# sousvide.net
KiCad netlist of a schematic drawn in EAGLE
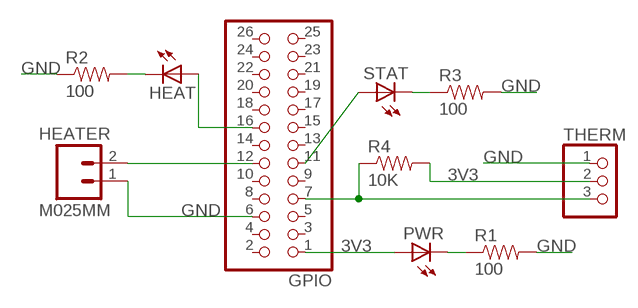
[diagram p0: schematic, sheet 1]

(export (version "E")
  (design (tool "Eeschema 10.0.6"))
  (components
    (comp (ref "GPIO")
      (value "PINHD-2X13")
      (footprint "eagle-import:2X13")
      (libsource (lib "eagle-import") (part "PINHD-2X13"))
    )
    (comp (ref "HEAT")
      (value "LED1206")
      (footprint "eagle-import:LED-1206")
      (libsource (lib "eagle-import") (part "LED1206"))
    )
    (comp (ref "HEATER")
      (value "M025MM")
      (footprint "eagle-import:SCREWTERMINAL-5MM-2")
      (libsource (lib "eagle-import") (part "M025MM"))
    )
    (comp (ref "PWR")
      (value "LED1206")
      (footprint "eagle-import:LED-1206")
      (libsource (lib "eagle-import") (part "LED1206"))
    )
    (comp (ref "R1")
      (value "100")
      (footprint "eagle-import:1206")
      (libsource (lib "eagle-import") (part "RESISTOR1206"))
    )
    (comp (ref "R2")
      (value "100")
      (footprint "eagle-import:1206")
      (libsource (lib "eagle-import") (part "SparkFun-Resistors_RESISTOR1206"))
    )
    (comp (ref "R3")
      (value "100")
      (footprint "eagle-import:1206")
      (libsource (lib "eagle-import") (part "RESISTOR1206"))
    )
    (comp (ref "R4")
      (value "10K")
      (footprint "eagle-import:1206")
      (libsource (lib "eagle-import") (part "RESISTOR1206"))
    )
    (comp (ref "STAT")
      (value "LED1206")
      (footprint "eagle-import:LED-1206")
      (libsource (lib "eagle-import") (part "LED1206"))
    )
    (comp (ref "THERM")
      (value "PINHD-1X3")
      (footprint "eagle-import:1X03")
      (libsource (lib "eagle-import") (part "PINHD-1X3"))
    )
  )
  (nets
    (net (code "1") (name "/3V3") (class "Default")
      (node (ref "GPIO") (pin "1") (pinfunction "1_1") (pintype "passive"))
      (node (ref "PWR") (pin "A") (pinfunction "A_A") (pintype "passive"))
      (node (ref "R4") (pin "2") (pinfunction "2_2") (pintype "passive"))
      (node (ref "THERM") (pin "2") (pinfunction "2_2") (pintype "passive"))
    )
    (net (code "2") (name "/GND") (class "Default")
      (node (ref "GPIO") (pin "6") (pinfunction "6_6") (pintype "passive"))
      (node (ref "HEATER") (pin "1") (pinfunction "1_1") (pintype "passive"))
      (node (ref "R1") (pin "2") (pinfunction "2_2") (pintype "passive"))
      (node (ref "R2") (pin "1") (pinfunction "1_1") (pintype "passive"))
      (node (ref "R3") (pin "2") (pinfunction "2_2") (pintype "passive"))
      (node (ref "THERM") (pin "1") (pinfunction "1_1") (pintype "passive"))
    )
    (net (code "3") (name "Net-(GPIO-Pad7)") (class "Default")
      (node (ref "GPIO") (pin "7") (pinfunction "7_7") (pintype "passive"))
      (node (ref "R4") (pin "1") (pinfunction "1_1") (pintype "passive"))
      (node (ref "THERM") (pin "3") (pinfunction "3_3") (pintype "passive"))
    )
    (net (code "4") (name "Net-(GPIO-Pad11)") (class "Default")
      (node (ref "GPIO") (pin "11") (pinfunction "11_11") (pintype "passive"))
      (node (ref "STAT") (pin "A") (pinfunction "A_A") (pintype "passive"))
    )
    (net (code "5") (name "Net-(GPIO-Pad12)") (class "Default")
      (node (ref "GPIO") (pin "12") (pinfunction "12_12") (pintype "passive"))
      (node (ref "HEATER") (pin "2") (pinfunction "2_2") (pintype "passive"))
    )
    (net (code "6") (name "Net-(GPIO-Pad16)") (class "Default")
      (node (ref "GPIO") (pin "16") (pinfunction "16_16") (pintype "passive"))
      (node (ref "HEAT") (pin "A") (pinfunction "A_A") (pintype "passive"))
    )
    (net (code "7") (name "Net-(HEAT-PadC)") (class "Default")
      (node (ref "HEAT") (pin "C") (pinfunction "C_C") (pintype "passive"))
      (node (ref "R2") (pin "2") (pinfunction "2_2") (pintype "passive"))
    )
    (net (code "8") (name "Net-(PWR-PadC)") (class "Default")
      (node (ref "PWR") (pin "C") (pinfunction "C_C") (pintype "passive"))
      (node (ref "R1") (pin "1") (pinfunction "1_1") (pintype "passive"))
    )
    (net (code "9") (name "Net-(R3-Pad1)") (class "Default")
      (node (ref "R3") (pin "1") (pinfunction "1_1") (pintype "passive"))
      (node (ref "STAT") (pin "C") (pinfunction "C_C") (pintype "passive"))
    )
    (net (code "10") (name "unconnected-(GPIO-Pad2)") (class "Default")
      (node (ref "GPIO") (pin "2") (pinfunction "2_2") (pintype "passive"))
    )
    (net (code "11") (name "unconnected-(GPIO-Pad3)") (class "Default")
      (node (ref "GPIO") (pin "3") (pinfunction "3_3") (pintype "passive"))
    )
    (net (code "12") (name "unconnected-(GPIO-Pad4)") (class "Default")
      (node (ref "GPIO") (pin "4") (pinfunction "4_4") (pintype "passive"))
    )
    (net (code "13") (name "unconnected-(GPIO-Pad5)") (class "Default")
      (node (ref "GPIO") (pin "5") (pinfunction "5_5") (pintype "passive"))
    )
    (net (code "14") (name "unconnected-(GPIO-Pad8)") (class "Default")
      (node (ref "GPIO") (pin "8") (pinfunction "8_8") (pintype "passive"))
    )
    (net (code "15") (name "unconnected-(GPIO-Pad9)") (class "Default")
      (node (ref "GPIO") (pin "9") (pinfunction "9_9") (pintype "passive"))
    )
    (net (code "16") (name "unconnected-(GPIO-Pad10)") (class "Default")
      (node (ref "GPIO") (pin "10") (pinfunction "10_10") (pintype "passive"))
    )
    (net (code "17") (name "unconnected-(GPIO-Pad13)") (class "Default")
      (node (ref "GPIO") (pin "13") (pinfunction "13_13") (pintype "passive"))
    )
    (net (code "18") (name "unconnected-(GPIO-Pad14)") (class "Default")
      (node (ref "GPIO") (pin "14") (pinfunction "14_14") (pintype "passive"))
    )
    (net (code "19") (name "unconnected-(GPIO-Pad15)") (class "Default")
      (node (ref "GPIO") (pin "15") (pinfunction "15_15") (pintype "passive"))
    )
    (net (code "20") (name "unconnected-(GPIO-Pad17)") (class "Default")
      (node (ref "GPIO") (pin "17") (pinfunction "17_17") (pintype "passive"))
    )
    (net (code "21") (name "unconnected-(GPIO-Pad18)") (class "Default")
      (node (ref "GPIO") (pin "18") (pinfunction "18_18") (pintype "passive"))
    )
    (net (code "22") (name "unconnected-(GPIO-Pad19)") (class "Default")
      (node (ref "GPIO") (pin "19") (pinfunction "19_19") (pintype "passive"))
    )
    (net (code "23") (name "unconnected-(GPIO-Pad20)") (class "Default")
      (node (ref "GPIO") (pin "20") (pinfunction "20_20") (pintype "passive"))
    )
    (net (code "24") (name "unconnected-(GPIO-Pad21)") (class "Default")
      (node (ref "GPIO") (pin "21") (pinfunction "21_21") (pintype "passive"))
    )
    (net (code "25") (name "unconnected-(GPIO-Pad22)") (class "Default")
      (node (ref "GPIO") (pin "22") (pinfunction "22_22") (pintype "passive"))
    )
    (net (code "26") (name "unconnected-(GPIO-Pad23)") (class "Default")
      (node (ref "GPIO") (pin "23") (pinfunction "23_23") (pintype "passive"))
    )
    (net (code "27") (name "unconnected-(GPIO-Pad24)") (class "Default")
      (node (ref "GPIO") (pin "24") (pinfunction "24_24") (pintype "passive"))
    )
    (net (code "28") (name "unconnected-(GPIO-Pad25)") (class "Default")
      (node (ref "GPIO") (pin "25") (pinfunction "25_25") (pintype "passive"))
    )
    (net (code "29") (name "unconnected-(GPIO-Pad26)") (class "Default")
      (node (ref "GPIO") (pin "26") (pinfunction "26_26") (pintype "passive"))
    )
  )
)
